# STB_MCU.net
KiCad netlist of a schematic drawn in Altium Designer
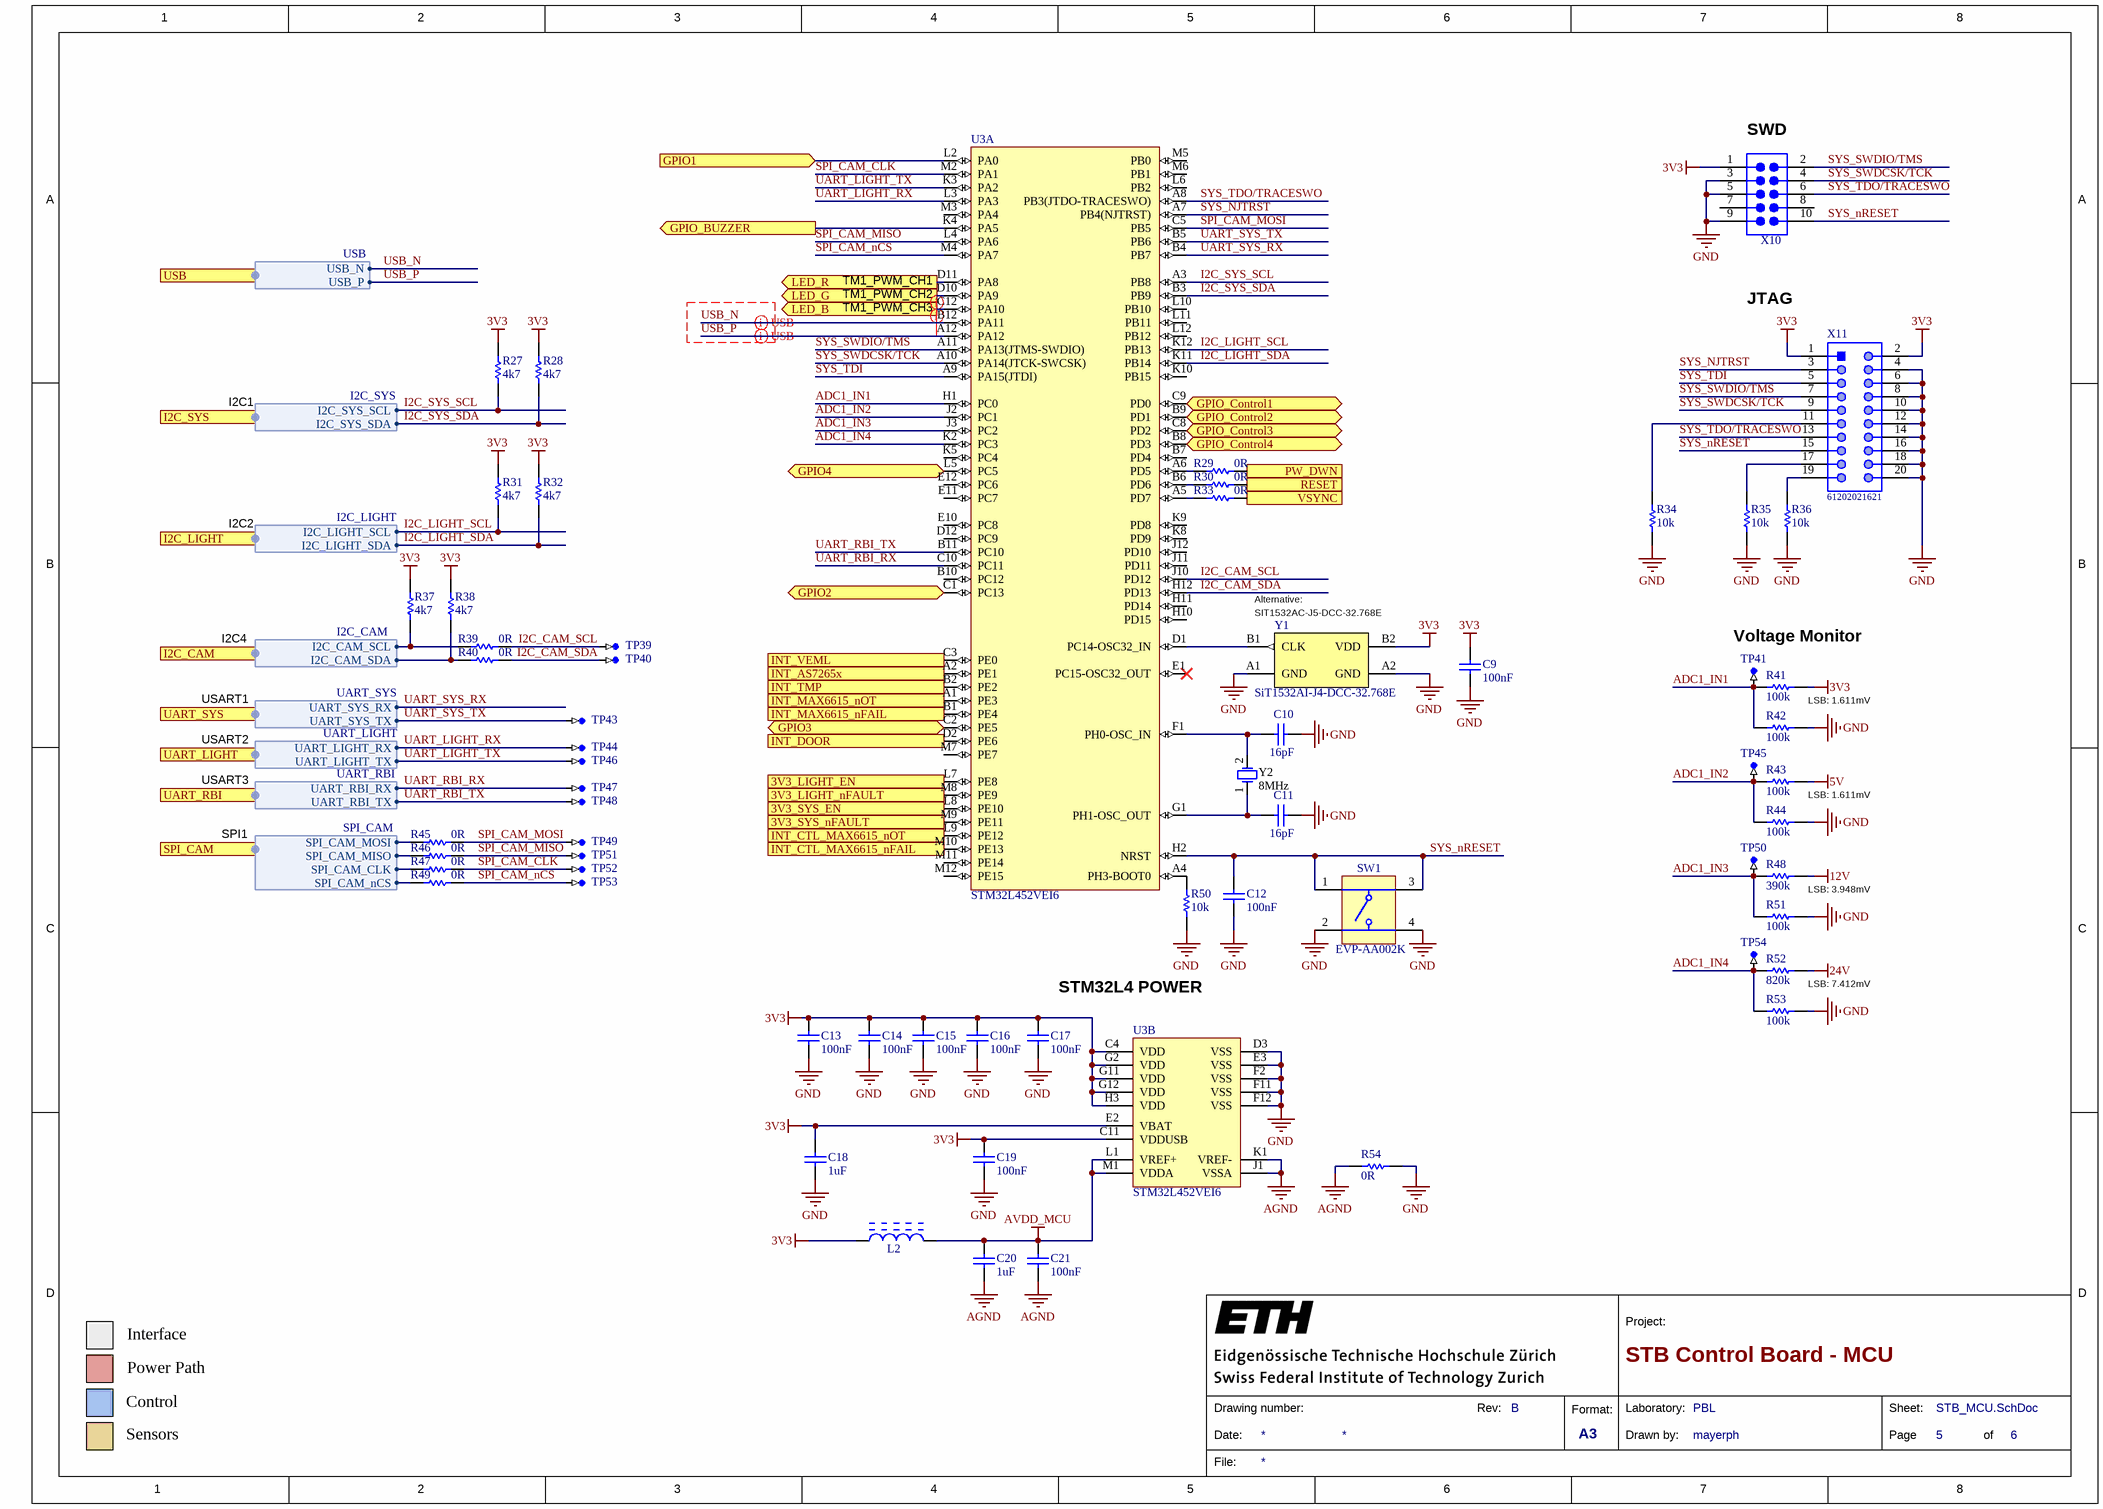
[diagram p0: STB_MCU.SchDoc]

(export (version "E")
  (design (tool "Eeschema 10.0.6"))
  (components
    (comp (ref "C9")
      (value "100nF")
      (footprint "CAPC1050X55X23LL05T13")
      (description "Chip Capacitor, 100 nF, +/- 10%, 16 V, -55 to 125 degC, 0402 (1005 Metric), RoHS, Tape and Reel")
      (fields
        (field (name "MANUFACTURER") "Samsung Electro-Mechanics")
        (field (name "MANUFACTURER PART NUMBER") "CL05B104KO5NNNC")
      )
      (libsource (lib "Altium Content Vault") (part "CAP-NP-2"))
    )
    (comp (ref "C10")
      (value "16pF")
      (footprint "CAPC1005X55X25LL05T10")
      (fields (field (name "MANUFACTURER") "Murata") (field (name "PART NUMBER") "GRM1555C1H160JA01D"))
      (libsource (lib "Altium Content Vault") (part "CAP"))
    )
    (comp (ref "C11")
      (value "16pF")
      (footprint "CAPC1005X55X25LL05T10")
      (fields (field (name "MANUFACTURER") "Murata") (field (name "PART NUMBER") "GRM1555C1H160JA01D"))
      (libsource (lib "Altium Content Vault") (part "CAP"))
    )
    (comp (ref "C12")
      (value "100nF")
      (footprint "CAPC1050X55X23LL05T13")
      (description "Chip Capacitor, 100 nF, +/- 10%, 16 V, -55 to 125 degC, 0402 (1005 Metric), RoHS, Tape and Reel")
      (fields
        (field (name "MANUFACTURER") "Samsung Electro-Mechanics")
        (field (name "MANUFACTURER PART NUMBER") "CL05B104KO5NNNC")
      )
      (libsource (lib "Altium Content Vault") (part "CAP-NP-2"))
    )
    (comp (ref "C13")
      (value "100nF")
      (footprint "CAPC1050X55X23LL05T13")
      (description "Chip Capacitor, 100 nF, +/- 10%, 16 V, -55 to 125 degC, 0402 (1005 Metric), RoHS, Tape and Reel")
      (fields
        (field (name "MANUFACTURER") "Samsung Electro-Mechanics")
        (field (name "MANUFACTURER PART NUMBER") "CL05B104KO5NNNC")
      )
      (libsource (lib "Altium Content Vault") (part "CAP-NP-2"))
    )
    (comp (ref "C14")
      (value "100nF")
      (footprint "CAPC1050X55X23LL05T13")
      (description "Chip Capacitor, 100 nF, +/- 10%, 16 V, -55 to 125 degC, 0402 (1005 Metric), RoHS, Tape and Reel")
      (fields
        (field (name "MANUFACTURER") "Samsung Electro-Mechanics")
        (field (name "MANUFACTURER PART NUMBER") "CL05B104KO5NNNC")
      )
      (libsource (lib "Altium Content Vault") (part "CAP-NP-2"))
    )
    (comp (ref "C15")
      (value "100nF")
      (footprint "CAPC1050X55X23LL05T13")
      (description "Chip Capacitor, 100 nF, +/- 10%, 16 V, -55 to 125 degC, 0402 (1005 Metric), RoHS, Tape and Reel")
      (fields
        (field (name "MANUFACTURER") "Samsung Electro-Mechanics")
        (field (name "MANUFACTURER PART NUMBER") "CL05B104KO5NNNC")
      )
      (libsource (lib "Altium Content Vault") (part "CAP-NP-2"))
    )
    (comp (ref "C16")
      (value "100nF")
      (footprint "CAPC1050X55X23LL05T13")
      (description "Chip Capacitor, 100 nF, +/- 10%, 16 V, -55 to 125 degC, 0402 (1005 Metric), RoHS, Tape and Reel")
      (fields
        (field (name "MANUFACTURER") "Samsung Electro-Mechanics")
        (field (name "MANUFACTURER PART NUMBER") "CL05B104KO5NNNC")
      )
      (libsource (lib "Altium Content Vault") (part "CAP-NP-2"))
    )
    (comp (ref "C17")
      (value "100nF")
      (footprint "CAPC1050X55X23LL05T13")
      (description "Chip Capacitor, 100 nF, +/- 10%, 16 V, -55 to 125 degC, 0402 (1005 Metric), RoHS, Tape and Reel")
      (fields
        (field (name "MANUFACTURER") "Samsung Electro-Mechanics")
        (field (name "MANUFACTURER PART NUMBER") "CL05B104KO5NNNC")
      )
      (libsource (lib "Altium Content Vault") (part "CAP-NP-2"))
    )
    (comp (ref "C18")
      (value "1uF")
      (footprint "CAPC1608X90X35LL15T15")
      (fields (field (name "MANUFACTURER") "Kemet") (field (name "PART NUMBER") "C0603C105K4RACTU"))
      (libsource (lib "Altium Content Vault") (part "CAP"))
    )
    (comp (ref "C19")
      (value "100nF")
      (footprint "CAPC1050X55X23LL05T13")
      (description "Chip Capacitor, 100 nF, +/- 10%, 16 V, -55 to 125 degC, 0402 (1005 Metric), RoHS, Tape and Reel")
      (fields
        (field (name "MANUFACTURER") "Samsung Electro-Mechanics")
        (field (name "MANUFACTURER PART NUMBER") "CL05B104KO5NNNC")
      )
      (libsource (lib "Altium Content Vault") (part "CAP-NP-2"))
    )
    (comp (ref "C20")
      (value "1uF")
      (footprint "CAPC1608X90X35LL15T15")
      (fields (field (name "MANUFACTURER") "Kemet") (field (name "PART NUMBER") "C0603C105K4RACTU"))
      (libsource (lib "Altium Content Vault") (part "CAP"))
    )
    (comp (ref "C21")
      (value "100nF")
      (footprint "CAPC1050X55X23LL05T13")
      (description "Chip Capacitor, 100 nF, +/- 10%, 16 V, -55 to 125 degC, 0402 (1005 Metric), RoHS, Tape and Reel")
      (fields
        (field (name "MANUFACTURER") "Samsung Electro-Mechanics")
        (field (name "MANUFACTURER PART NUMBER") "CL05B104KO5NNNC")
      )
      (libsource (lib "Altium Content Vault") (part "CAP-NP-2"))
    )
    (comp (ref "L2")
      (value "LI0402E300R-10")
      (footprint "INDC1005X07L")
      (description "30 Ohm 1 Power, Signal Line Ferrite Bead 0402 (1005 Metric) 500mA 300 mOhm Max DCR")
      (fields (field (name "MANUFACTURER") "Laird-Signal Integrity Products"))
      (libsource (lib "ETHZ Vault") (part "Ferrite Bead"))
    )
    (comp (ref "R27")
      (value "4k7")
      (footprint "RESC1005X40X25LL05T10")
      (fields
        (field (name "MANUFACTURER") "Yageo / Phycomp")
        (field (name "PART NUMBER") "RC0402FR-074K7L")
        (field (name "TOLERANCE") "1%")
      )
      (libsource (lib "Altium Content Vault") (part "RES"))
    )
    (comp (ref "R28")
      (value "4k7")
      (footprint "RESC1005X40X25LL05T10")
      (fields
        (field (name "MANUFACTURER") "Yageo / Phycomp")
        (field (name "PART NUMBER") "RC0402FR-074K7L")
        (field (name "TOLERANCE") "1%")
      )
      (libsource (lib "Altium Content Vault") (part "RES"))
    )
    (comp (ref "R29")
      (value "0R")
      (footprint "RESC1005X40X25LL05T10")
      (fields (field (name "MANUFACTURER") "Yageo / Phycomp") (field (name "PART NUMBER") "RC0402JR-070RL"))
      (libsource (lib "Altium Content Vault") (part "RES"))
    )
    (comp (ref "R30")
      (value "0R")
      (footprint "RESC1005X40X25LL05T10")
      (fields (field (name "MANUFACTURER") "Yageo / Phycomp") (field (name "PART NUMBER") "RC0402JR-070RL"))
      (libsource (lib "Altium Content Vault") (part "RES"))
    )
    (comp (ref "R31")
      (value "4k7")
      (footprint "RESC1005X40X25LL05T10")
      (fields
        (field (name "MANUFACTURER") "Yageo / Phycomp")
        (field (name "PART NUMBER") "RC0402FR-074K7L")
        (field (name "TOLERANCE") "1%")
      )
      (libsource (lib "Altium Content Vault") (part "RES"))
    )
    (comp (ref "R32")
      (value "4k7")
      (footprint "RESC1005X40X25LL05T10")
      (fields
        (field (name "MANUFACTURER") "Yageo / Phycomp")
        (field (name "PART NUMBER") "RC0402FR-074K7L")
        (field (name "TOLERANCE") "1%")
      )
      (libsource (lib "Altium Content Vault") (part "RES"))
    )
    (comp (ref "R33")
      (value "0R")
      (footprint "RESC1005X40X25LL05T10")
      (fields (field (name "MANUFACTURER") "Yageo / Phycomp") (field (name "PART NUMBER") "RC0402JR-070RL"))
      (libsource (lib "Altium Content Vault") (part "RES"))
    )
    (comp (ref "R34")
      (value "10k")
      (footprint "RESC1005X40X25LL05T05")
      (description "Chip Resistor, 10 KOhm, +/- 1%, 0.1 W, -55 to 155 degC, 0402 (1005 Metric), RoHS, Tape and Reel")
      (fields (field (name "TOLERANCE") "1%") (field (name "MANUFACTURER") "Panasonic"))
      (libsource (lib "Altium Content Vault") (part "RES-2"))
    )
    (comp (ref "R35")
      (value "10k")
      (footprint "RESC1005X40X25LL05T05")
      (description "Chip Resistor, 10 KOhm, +/- 1%, 0.1 W, -55 to 155 degC, 0402 (1005 Metric), RoHS, Tape and Reel")
      (fields (field (name "TOLERANCE") "1%") (field (name "MANUFACTURER") "Panasonic"))
      (libsource (lib "Altium Content Vault") (part "RES-2"))
    )
    (comp (ref "R36")
      (value "10k")
      (footprint "RESC1005X40X25LL05T05")
      (description "Chip Resistor, 10 KOhm, +/- 1%, 0.1 W, -55 to 155 degC, 0402 (1005 Metric), RoHS, Tape and Reel")
      (fields (field (name "TOLERANCE") "1%") (field (name "MANUFACTURER") "Panasonic"))
      (libsource (lib "Altium Content Vault") (part "RES-2"))
    )
    (comp (ref "R37")
      (value "4k7")
      (footprint "RESC1005X40X25LL05T10")
      (fields
        (field (name "MANUFACTURER") "Yageo / Phycomp")
        (field (name "PART NUMBER") "RC0402FR-074K7L")
        (field (name "TOLERANCE") "1%")
      )
      (libsource (lib "Altium Content Vault") (part "RES"))
    )
    (comp (ref "R38")
      (value "4k7")
      (footprint "RESC1005X40X25LL05T10")
      (fields
        (field (name "MANUFACTURER") "Yageo / Phycomp")
        (field (name "PART NUMBER") "RC0402FR-074K7L")
        (field (name "TOLERANCE") "1%")
      )
      (libsource (lib "Altium Content Vault") (part "RES"))
    )
    (comp (ref "R39")
      (value "0R")
      (footprint "RESC1005X40X25LL05T10")
      (fields (field (name "MANUFACTURER") "Yageo / Phycomp") (field (name "PART NUMBER") "RC0402JR-070RL"))
      (libsource (lib "Altium Content Vault") (part "RES"))
    )
    (comp (ref "R40")
      (value "0R")
      (footprint "RESC1005X40X25LL05T10")
      (fields (field (name "MANUFACTURER") "Yageo / Phycomp") (field (name "PART NUMBER") "RC0402JR-070RL"))
      (libsource (lib "Altium Content Vault") (part "RES"))
    )
    (comp (ref "R41")
      (value "100k")
      (footprint "RESC1005X40X25LL05T10")
      (fields
        (field (name "PART NUMBER") "RC0402FR-07100KL")
        (field (name "MANUFACTURER") "Yageo / Phycomp")
        (field (name "TOLERANCE") "1%")
      )
      (libsource (lib "Altium Content Vault") (part "RES"))
    )
    (comp (ref "R42")
      (value "100k")
      (footprint "RESC1005X40X25LL05T10")
      (fields
        (field (name "PART NUMBER") "RC0402FR-07100KL")
        (field (name "MANUFACTURER") "Yageo / Phycomp")
        (field (name "TOLERANCE") "1%")
      )
      (libsource (lib "Altium Content Vault") (part "RES"))
    )
    (comp (ref "R43")
      (value "100k")
      (footprint "RESC1005X40X25LL05T10")
      (fields
        (field (name "PART NUMBER") "RC0402FR-07100KL")
        (field (name "MANUFACTURER") "Yageo / Phycomp")
        (field (name "TOLERANCE") "1%")
      )
      (libsource (lib "Altium Content Vault") (part "RES"))
    )
    (comp (ref "R44")
      (value "100k")
      (footprint "RESC1005X40X25LL05T10")
      (fields
        (field (name "PART NUMBER") "RC0402FR-07100KL")
        (field (name "MANUFACTURER") "Yageo / Phycomp")
        (field (name "TOLERANCE") "1%")
      )
      (libsource (lib "Altium Content Vault") (part "RES"))
    )
    (comp (ref "R45")
      (value "0R")
      (footprint "RESC1005X40X25LL05T10")
      (fields (field (name "MANUFACTURER") "Yageo / Phycomp") (field (name "PART NUMBER") "RC0402JR-070RL"))
      (libsource (lib "Altium Content Vault") (part "RES"))
    )
    (comp (ref "R46")
      (value "0R")
      (footprint "RESC1005X40X25LL05T10")
      (fields (field (name "MANUFACTURER") "Yageo / Phycomp") (field (name "PART NUMBER") "RC0402JR-070RL"))
      (libsource (lib "Altium Content Vault") (part "RES"))
    )
    (comp (ref "R47")
      (value "0R")
      (footprint "RESC1005X40X25LL05T10")
      (fields (field (name "MANUFACTURER") "Yageo / Phycomp") (field (name "PART NUMBER") "RC0402JR-070RL"))
      (libsource (lib "Altium Content Vault") (part "RES"))
    )
    (comp (ref "R48")
      (value "390k")
      (footprint "RESC1005X40X25LL05T05")
      (fields
        (field (name "PART NUMBER") "ERJ2RKF3903X")
        (field (name "MANUFACTURER") "Panasonic")
        (field (name "MANUFACTURER PART NUMBER") "ERJ-2RKF3903X")
      )
      (libsource (lib "Altium Content Vault") (part "RES"))
    )
    (comp (ref "R49")
      (value "0R")
      (footprint "RESC1005X40X25LL05T10")
      (fields (field (name "MANUFACTURER") "Yageo / Phycomp") (field (name "PART NUMBER") "RC0402JR-070RL"))
      (libsource (lib "Altium Content Vault") (part "RES"))
    )
    (comp (ref "R50")
      (value "10k")
      (footprint "RESC1005X40X25LL05T05")
      (description "Chip Resistor, 10 KOhm, +/- 1%, 0.1 W, -55 to 155 degC, 0402 (1005 Metric), RoHS, Tape and Reel")
      (fields (field (name "TOLERANCE") "1%") (field (name "MANUFACTURER") "Panasonic"))
      (libsource (lib "Altium Content Vault") (part "RES-2"))
    )
    (comp (ref "R51")
      (value "100k")
      (footprint "RESC1005X40X25LL05T10")
      (fields
        (field (name "PART NUMBER") "RC0402FR-07100KL")
        (field (name "MANUFACTURER") "Yageo / Phycomp")
        (field (name "TOLERANCE") "1%")
      )
      (libsource (lib "Altium Content Vault") (part "RES"))
    )
    (comp (ref "R52")
      (value "820k")
      (footprint "RESC1005X40X25LL05T05")
      (fields
        (field (name "PART NUMBER") "CRCW0402820KFKED")
        (field (name "MANUFACTURER") "Vishay Dale")
        (field (name "TOLERANCE") "1%")
      )
      (libsource (lib "Altium Content Vault") (part "RES"))
    )
    (comp (ref "R53")
      (value "100k")
      (footprint "RESC1005X40X25LL05T10")
      (fields
        (field (name "PART NUMBER") "RC0402FR-07100KL")
        (field (name "MANUFACTURER") "Yageo / Phycomp")
        (field (name "TOLERANCE") "1%")
      )
      (libsource (lib "Altium Content Vault") (part "RES"))
    )
    (comp (ref "R54")
      (value "0R")
      (footprint "RESC1005X40X25LL05T10")
      (fields (field (name "MANUFACTURER") "Yageo / Phycomp") (field (name "PART NUMBER") "RC0402JR-070RL"))
      (libsource (lib "Altium Content Vault") (part "RES"))
    )
    (comp (ref "SW1")
      (value "EVP-AA002K")
      (footprint "PNSC-EVPAA_V")
      (description "Light Touch Switch, 100 mOhm, -40 to 85 degC, 4-Pin SMD, RoHS, Tape and Reel")
      (fields (field (name "MANUFACTURER") "Panasonic"))
      (libsource (lib "Altium Content Vault") (part "SW-SPST-4"))
    )
    (comp (ref "TP39")
      (value "TP_1mm")
      (footprint "TP-SM-C-100")
      (description "testPoint 1mm")
      (libsource (lib "STB_Schlib") (part "testPoint_1mm"))
    )
    (comp (ref "TP40")
      (value "TP_1mm")
      (footprint "TP-SM-C-100")
      (description "testPoint 1mm")
      (libsource (lib "STB_Schlib") (part "testPoint_1mm"))
    )
    (comp (ref "TP41")
      (value "TP_1mm")
      (footprint "TP-SM-C-100")
      (description "testPoint 1mm")
      (libsource (lib "STB_Schlib") (part "testPoint_1mm"))
    )
    (comp (ref "TP43")
      (value "TP_1mm")
      (footprint "TP-SM-C-100")
      (description "testPoint 1mm")
      (libsource (lib "STB_Schlib") (part "testPoint_1mm"))
    )
    (comp (ref "TP44")
      (value "TP_1mm")
      (footprint "TP-SM-C-100")
      (description "testPoint 1mm")
      (libsource (lib "STB_Schlib") (part "testPoint_1mm"))
    )
    (comp (ref "TP45")
      (value "TP_1mm")
      (footprint "TP-SM-C-100")
      (description "testPoint 1mm")
      (libsource (lib "STB_Schlib") (part "testPoint_1mm"))
    )
    (comp (ref "TP46")
      (value "TP_1mm")
      (footprint "TP-SM-C-100")
      (description "testPoint 1mm")
      (libsource (lib "STB_Schlib") (part "testPoint_1mm"))
    )
    (comp (ref "TP47")
      (value "TP_1mm")
      (footprint "TP-SM-C-100")
      (description "testPoint 1mm")
      (libsource (lib "STB_Schlib") (part "testPoint_1mm"))
    )
    (comp (ref "TP48")
      (value "TP_1mm")
      (footprint "TP-SM-C-100")
      (description "testPoint 1mm")
      (libsource (lib "STB_Schlib") (part "testPoint_1mm"))
    )
    (comp (ref "TP49")
      (value "TP_1mm")
      (footprint "TP-SM-C-100")
      (description "testPoint 1mm")
      (libsource (lib "STB_Schlib") (part "testPoint_1mm"))
    )
    (comp (ref "TP50")
      (value "TP_1mm")
      (footprint "TP-SM-C-100")
      (description "testPoint 1mm")
      (libsource (lib "STB_Schlib") (part "testPoint_1mm"))
    )
    (comp (ref "TP51")
      (value "TP_1mm")
      (footprint "TP-SM-C-100")
      (description "testPoint 1mm")
      (libsource (lib "STB_Schlib") (part "testPoint_1mm"))
    )
    (comp (ref "TP52")
      (value "TP_1mm")
      (footprint "TP-SM-C-100")
      (description "testPoint 1mm")
      (libsource (lib "STB_Schlib") (part "testPoint_1mm"))
    )
    (comp (ref "TP53")
      (value "TP_1mm")
      (footprint "TP-SM-C-100")
      (description "testPoint 1mm")
      (libsource (lib "STB_Schlib") (part "testPoint_1mm"))
    )
    (comp (ref "TP54")
      (value "TP_1mm")
      (footprint "TP-SM-C-100")
      (description "testPoint 1mm")
      (libsource (lib "STB_Schlib") (part "testPoint_1mm"))
    )
    (comp (ref "U3")
      (value "STM32L452VEI6")
      (footprint "UFBGA100")
      (description "IC MCU 32BIT 512KB FLASH 100UFBGA")
      (fields (field (name "MANUFACTURER") "STMicroelectronics"))
      (libsource (lib "") (part "STM32L452-UFBGA-100_1"))
    )
    (comp (ref "X10")
      (value "3220-10-0100-00")
      (footprint "3220-10-0100-00")
      (description "BOX HEADER, 0.050 5x2 POS")
      (fields (field (name "MANUFACTURER") "CNC Tech"))
      (libsource (lib "ETHZ Vault") (part "CON-5x2-Male"))
    )
    (comp (ref "X11")
      (value "61202021621")
      (footprint "61202021621")
      (description "Male Box Header WR-BHD, THT, Vertical, pitch 2.54 mm, 20 pins")
      (fields (field (name "MANUFACTURER") "Wurth Elektronik") (field (name "PUBLISHER") "WurthElektronik"))
      (libsource (lib "Altium Content Vault") (part "WE-CN-2P-M-R20"))
    )
    (comp (ref "Y1")
      (value "SiT1532AI-J4-DCC-32.768E")
      (footprint "4-UFBGA")
      (fields (field (name "MANUFACTURER") "SiTime"))
      (libsource (lib "ETHZ Vault") (part "SiT1552"))
    )
    (comp (ref "Y2")
      (value "8MHz")
      (footprint "NDK-NX3225GD-8MHZ-STD-CRA-3_V")
      (description "Crystal Unit, 8 MHz, 8 pF, -40 to 150 degC, 2-Pin SMD, RoHS, Tape and Reel")
      (fields
        (field (name "MANUFACTURER") "NDK")
        (field (name "MANUFACTURER PART NUMBER") "NX3225GD-8MHZ-STD-CRA-3")
      )
      (libsource (lib "Altium Content Vault") (part "XTAL-1-2-2"))
    )
  )
  (nets
    (net (code "9") (name "/3V3_LIGHT_EN") (class "Default")
      (node (ref "U3") (pin "L7") (pinfunction "PE8_L7") (pintype "bidirectional"))
    )
    (net (code "10") (name "/3V3_LIGHT_nFAULT") (class "Default")
      (node (ref "U3") (pin "M8") (pinfunction "PE9_M8") (pintype "bidirectional"))
    )
    (net (code "11") (name "/3V3_SYS_EN") (class "Default")
      (node (ref "U3") (pin "L8") (pinfunction "PE10_L8") (pintype "bidirectional"))
    )
    (net (code "12") (name "/3V3_SYS_nFAULT") (class "Default")
      (node (ref "U3") (pin "M9") (pinfunction "PE11_M9") (pintype "bidirectional"))
    )
    (net (code "13") (name "/ADC1_IN1") (class "Default")
      (node (ref "R41") (pin "2") (pinfunction "2_2") (pintype "passive"))
      (node (ref "R42") (pin "2") (pinfunction "2_2") (pintype "passive"))
      (node (ref "TP41") (pin "TP") (pinfunction "TP_TP") (pintype "input"))
      (node (ref "U3") (pin "H1") (pinfunction "PC0_H1") (pintype "bidirectional"))
    )
    (net (code "14") (name "/ADC1_IN2") (class "Default")
      (node (ref "R43") (pin "2") (pinfunction "2_2") (pintype "passive"))
      (node (ref "R44") (pin "2") (pinfunction "2_2") (pintype "passive"))
      (node (ref "TP45") (pin "TP") (pinfunction "TP_TP") (pintype "input"))
      (node (ref "U3") (pin "J2") (pinfunction "PC1_J2") (pintype "bidirectional"))
    )
    (net (code "15") (name "/ADC1_IN3") (class "Default")
      (node (ref "R48") (pin "1") (pinfunction "1_1") (pintype "passive"))
      (node (ref "R51") (pin "2") (pinfunction "2_2") (pintype "passive"))
      (node (ref "TP50") (pin "TP") (pinfunction "TP_TP") (pintype "input"))
      (node (ref "U3") (pin "J3") (pinfunction "PC2_J3") (pintype "bidirectional"))
    )
    (net (code "16") (name "/ADC1_IN4") (class "Default")
      (node (ref "R52") (pin "1") (pinfunction "1_1") (pintype "passive"))
      (node (ref "R53") (pin "2") (pinfunction "2_2") (pintype "passive"))
      (node (ref "TP54") (pin "TP") (pinfunction "TP_TP") (pintype "input"))
      (node (ref "U3") (pin "K2") (pinfunction "PC3_K2") (pintype "bidirectional"))
    )
    (net (code "17") (name "/GPIO1") (class "Default")
      (node (ref "U3") (pin "L2") (pinfunction "PA0_L2") (pintype "bidirectional"))
    )
    (net (code "18") (name "/GPIO2") (class "Default")
      (node (ref "U3") (pin "C1") (pinfunction "PC13_C1") (pintype "bidirectional"))
    )
    (net (code "19") (name "/GPIO3") (class "Default")
      (node (ref "U3") (pin "C2") (pinfunction "PE5_C2") (pintype "bidirectional"))
    )
    (net (code "20") (name "/GPIO4") (class "Default")
      (node (ref "U3") (pin "L5") (pinfunction "PC5_L5") (pintype "bidirectional"))
    )
    (net (code "21") (name "/GPIO_BUZZER") (class "Default")
      (node (ref "U3") (pin "K4") (pinfunction "PA5_K4") (pintype "bidirectional"))
    )
    (net (code "22") (name "/GPIO_Control1") (class "Default")
      (node (ref "U3") (pin "C9") (pinfunction "PD0_C9") (pintype "bidirectional"))
    )
    (net (code "23") (name "/GPIO_Control2") (class "Default")
      (node (ref "U3") (pin "B9") (pinfunction "PD1_B9") (pintype "bidirectional"))
    )
    (net (code "24") (name "/GPIO_Control3") (class "Default")
      (node (ref "U3") (pin "C8") (pinfunction "PD2_C8") (pintype "bidirectional"))
    )
    (net (code "25") (name "/GPIO_Control4") (class "Default")
      (node (ref "U3") (pin "B8") (pinfunction "PD3_B8") (pintype "bidirectional"))
    )
    (net (code "26") (name "/I2C_CAM_SCL") (class "Default")
      (node (ref "R39") (pin "2") (pinfunction "2_2") (pintype "passive"))
      (node (ref "TP39") (pin "TP") (pinfunction "TP_TP") (pintype "input"))
      (node (ref "U3") (pin "J10") (pinfunction "PD12_J10") (pintype "bidirectional"))
    )
    (net (code "27") (name "/I2C_CAM_SDA") (class "Default")
      (node (ref "R40") (pin "2") (pinfunction "2_2") (pintype "passive"))
      (node (ref "TP40") (pin "TP") (pinfunction "TP_TP") (pintype "input"))
      (node (ref "U3") (pin "H12") (pinfunction "PD13_H12") (pintype "bidirectional"))
    )
    (net (code "28") (name "/I2C_LIGHT_SCL") (class "Default")
      (node (ref "R31") (pin "1") (pinfunction "1_1") (pintype "passive"))
      (node (ref "U3") (pin "K12") (pinfunction "PB13_K12") (pintype "bidirectional"))
    )
    (net (code "29") (name "/I2C_LIGHT_SDA") (class "Default")
      (node (ref "R32") (pin "1") (pinfunction "1_1") (pintype "passive"))
      (node (ref "U3") (pin "K11") (pinfunction "PB14_K11") (pintype "bidirectional"))
    )
    (net (code "30") (name "/I2C_SYS_SCL") (class "Default")
      (node (ref "R27") (pin "1") (pinfunction "1_1") (pintype "passive"))
      (node (ref "U3") (pin "A3") (pinfunction "PB8_A3") (pintype "bidirectional"))
    )
    (net (code "31") (name "/I2C_SYS_SDA") (class "Default")
      (node (ref "R28") (pin "1") (pinfunction "1_1") (pintype "passive"))
      (node (ref "U3") (pin "B3") (pinfunction "PB9_B3") (pintype "bidirectional"))
    )
    (net (code "32") (name "/INT_AS7265x") (class "Default")
      (node (ref "U3") (pin "A2") (pinfunction "PE1_A2") (pintype "bidirectional"))
    )
    (net (code "33") (name "/INT_CTL_MAX6615_nFAIL") (class "Default")
      (node (ref "U3") (pin "M10") (pinfunction "PE13_M10") (pintype "bidirectional"))
    )
    (net (code "34") (name "/INT_CTL_MAX6615_nOT") (class "Default")
      (node (ref "U3") (pin "L9") (pinfunction "PE12_L9") (pintype "bidirectional"))
    )
    (net (code "35") (name "/INT_DOOR") (class "Default")
      (node (ref "U3") (pin "D2") (pinfunction "PE6_D2") (pintype "bidirectional"))
    )
    (net (code "36") (name "/INT_MAX6615_nFAIL") (class "Default")
      (node (ref "U3") (pin "B1") (pinfunction "PE4_B1") (pintype "bidirectional"))
    )
    (net (code "37") (name "/INT_MAX6615_nOT") (class "Default")
      (node (ref "U3") (pin "A1") (pinfunction "PE3_A1") (pintype "bidirectional"))
    )
    (net (code "38") (name "/INT_TMP") (class "Default")
      (node (ref "U3") (pin "B2") (pinfunction "PE2_B2") (pintype "bidirectional"))
    )
    (net (code "39") (name "/INT_VEML") (class "Default")
      (node (ref "U3") (pin "C3") (pinfunction "PE0_C3") (pintype "bidirectional"))
    )
    (net (code "40") (name "/LED_B") (class "Default")
      (node (ref "U3") (pin "C12") (pinfunction "PA10_C12") (pintype "bidirectional"))
    )
    (net (code "41") (name "/LED_G") (class "Default")
      (node (ref "U3") (pin "D10") (pinfunction "PA9_D10") (pintype "bidirectional"))
    )
    (net (code "42") (name "/LED_R") (class "Default")
      (node (ref "U3") (pin "D11") (pinfunction "PA8_D11") (pintype "bidirectional"))
    )
    (net (code "43") (name "/PW_DWN") (class "Default")
      (node (ref "R29") (pin "2") (pinfunction "2_2") (pintype "passive"))
    )
    (net (code "44") (name "/RESET") (class "Default")
      (node (ref "R30") (pin "2") (pinfunction "2_2") (pintype "passive"))
    )
    (net (code "45") (name "/SPI_CAM_CLK") (class "Default")
      (node (ref "R47") (pin "2") (pinfunction "2_2") (pintype "passive"))
      (node (ref "TP52") (pin "TP") (pinfunction "TP_TP") (pintype "input"))
      (node (ref "U3") (pin "M2") (pinfunction "PA1_M2") (pintype "bidirectional"))
    )
    (net (code "46") (name "/SPI_CAM_MISO") (class "Default")
      (node (ref "R46") (pin "2") (pinfunction "2_2") (pintype "passive"))
      (node (ref "TP51") (pin "TP") (pinfunction "TP_TP") (pintype "input"))
      (node (ref "U3") (pin "L4") (pinfunction "PA6_L4") (pintype "bidirectional"))
    )
    (net (code "47") (name "/SPI_CAM_MOSI") (class "Default")
      (node (ref "R45") (pin "2") (pinfunction "2_2") (pintype "passive"))
      (node (ref "TP49") (pin "TP") (pinfunction "TP_TP") (pintype "input"))
      (node (ref "U3") (pin "C5") (pinfunction "PB5_C5") (pintype "bidirectional"))
    )
    (net (code "48") (name "/SPI_CAM_nCS") (class "Default")
      (node (ref "R49") (pin "2") (pinfunction "2_2") (pintype "passive"))
      (node (ref "TP53") (pin "TP") (pinfunction "TP_TP") (pintype "input"))
      (node (ref "U3") (pin "M4") (pinfunction "PA7_M4") (pintype "bidirectional"))
    )
    (net (code "49") (name "/SYS_NJTRST") (class "Default")
      (node (ref "U3") (pin "A7") (pinfunction "PB4(NJTRST)_A7") (pintype "bidirectional"))
      (node (ref "X11") (pin "3") (pinfunction "3_3") (pintype "passive"))
    )
    (net (code "50") (name "/SYS_SWDCSK{slash}TCK") (class "Default")
      (node (ref "U3") (pin "A10") (pinfunction "PA14(JTCK-SWCSK)_A10") (pintype "bidirectional"))
      (node (ref "X10") (pin "4") (pinfunction "4_4") (pintype "passive"))
      (node (ref "X11") (pin "9") (pinfunction "9_9") (pintype "passive"))
    )
    (net (code "51") (name "/SYS_SWDIO{slash}TMS") (class "Default")
      (node (ref "U3") (pin "A11") (pinfunction "PA13(JTMS-SWDIO)_A11") (pintype "bidirectional"))
      (node (ref "X10") (pin "2") (pinfunction "2_2") (pintype "passive"))
      (node (ref "X11") (pin "7") (pinfunction "7_7") (pintype "passive"))
    )
    (net (code "52") (name "/SYS_TDI") (class "Default")
      (node (ref "U3") (pin "A9") (pinfunction "PA15(JTDI)_A9") (pintype "bidirectional"))
      (node (ref "X11") (pin "5") (pinfunction "5_5") (pintype "passive"))
    )
    (net (code "53") (name "/SYS_TDO{slash}TRACESWO") (class "Default")
      (node (ref "U3") (pin "A8") (pinfunction "PB3(JTDO-TRACESWO)_A8") (pintype "bidirectional"))
      (node (ref "X10") (pin "6") (pinfunction "6_6") (pintype "passive"))
      (node (ref "X11") (pin "13") (pinfunction "13_13") (pintype "passive"))
    )
    (net (code "54") (name "/SYS_nRESET") (class "Default")
      (node (ref "C12") (pin "2") (pinfunction "2_2") (pintype "passive"))
      (node (ref "SW1") (pin "1") (pinfunction "A_1") (pintype "passive"))
      (node (ref "SW1") (pin "3") (pinfunction "A'_3") (pintype "passive"))
      (node (ref "U3") (pin "H2") (pinfunction "NRST_H2") (pintype "bidirectional"))
      (node (ref "X10") (pin "10") (pinfunction "10_10") (pintype "passive"))
      (node (ref "X11") (pin "15") (pinfunction "15_15") (pintype "passive"))
    )
    (net (code "55") (name "/UART_LIGHT_RX") (class "Default")
      (node (ref "TP44") (pin "TP") (pinfunction "TP_TP") (pintype "input"))
      (node (ref "U3") (pin "L3") (pinfunction "PA3_L3") (pintype "bidirectional"))
    )
    (net (code "56") (name "/UART_LIGHT_TX") (class "Default")
      (node (ref "TP46") (pin "TP") (pinfunction "TP_TP") (pintype "input"))
      (node (ref "U3") (pin "K3") (pinfunction "PA2_K3") (pintype "bidirectional"))
    )
    (net (code "57") (name "/UART_RBI_RX") (class "Default")
      (node (ref "TP47") (pin "TP") (pinfunction "TP_TP") (pintype "input"))
      (node (ref "U3") (pin "C10") (pinfunction "PC11_C10") (pintype "bidirectional"))
    )
    (net (code "58") (name "/UART_RBI_TX") (class "Default")
      (node (ref "TP48") (pin "TP") (pinfunction "TP_TP") (pintype "input"))
      (node (ref "U3") (pin "B11") (pinfunction "PC10_B11") (pintype "bidirectional"))
    )
    (net (code "59") (name "/UART_SYS_RX") (class "Default")
      (node (ref "U3") (pin "B4") (pinfunction "PB7_B4") (pintype "bidirectional"))
    )
    (net (code "60") (name "/UART_SYS_TX") (class "Default")
      (node (ref "TP43") (pin "TP") (pinfunction "TP_TP") (pintype "input"))
      (node (ref "U3") (pin "B5") (pinfunction "PB6_B5") (pintype "bidirectional"))
    )
    (net (code "61") (name "/USB_N") (class "Default")
      (node (ref "U3") (pin "B12") (pinfunction "PA11_B12") (pintype "bidirectional"))
    )
    (net (code "62") (name "/USB_P") (class "Default")
      (node (ref "U3") (pin "A12") (pinfunction "PA12_A12") (pintype "bidirectional"))
    )
    (net (code "63") (name "/VSYNC") (class "Default")
      (node (ref "R33") (pin "2") (pinfunction "2_2") (pintype "passive"))
    )
    (net (code "72") (name "3V3") (class "Default")
      (node (ref "C13") (pin "2") (pinfunction "2_2") (pintype "passive"))
      (node (ref "C14") (pin "2") (pinfunction "2_2") (pintype "passive"))
      (node (ref "C15") (pin "2") (pinfunction "2_2") (pintype "passive"))
      (node (ref "C16") (pin "2") (pinfunction "2_2") (pintype "passive"))
      (node (ref "C17") (pin "2") (pinfunction "2_2") (pintype "passive"))
      (node (ref "C18") (pin "2") (pinfunction "2_2") (pintype "passive"))
      (node (ref "C19") (pin "2") (pinfunction "2_2") (pintype "passive"))
      (node (ref "C9") (pin "2") (pinfunction "2_2") (pintype "passive"))
      (node (ref "L2") (pin "1") (pinfunction "1_1") (pintype "passive"))
      (node (ref "R27") (pin "2") (pinfunction "2_2") (pintype "passive"))
      (node (ref "R28") (pin "2") (pinfunction "2_2") (pintype "passive"))
      (node (ref "R31") (pin "2") (pinfunction "2_2") (pintype "passive"))
      (node (ref "R32") (pin "2") (pinfunction "2_2") (pintype "passive"))
      (node (ref "R37") (pin "2") (pinfunction "2_2") (pintype "passive"))
      (node (ref "R38") (pin "2") (pinfunction "2_2") (pintype "passive"))
      (node (ref "R41") (pin "1") (pinfunction "1_1") (pintype "passive"))
      (node (ref "U3") (pin "C11") (pinfunction "VDDUSB_C11") (pintype "power_in"))
      (node (ref "U3") (pin "C4") (pinfunction "VDD_C4") (pintype "power_in"))
      (node (ref "U3") (pin "E2") (pinfunction "VBAT_E2") (pintype "power_in"))
      (node (ref "U3") (pin "G11") (pinfunction "VDD_G11") (pintype "power_in"))
      (node (ref "U3") (pin "G12") (pinfunction "VDD_G12") (pintype "power_in"))
      (node (ref "U3") (pin "G2") (pinfunction "VDD_G2") (pintype "power_in"))
      (node (ref "U3") (pin "H3") (pinfunction "VDD_H3") (pintype "power_in"))
      (node (ref "X10") (pin "1") (pinfunction "1_1") (pintype "passive"))
      (node (ref "X11") (pin "1") (pinfunction "1_1") (pintype "passive"))
      (node (ref "X11") (pin "2") (pinfunction "2_2") (pintype "passive"))
      (node (ref "Y1") (pin "B2") (pinfunction "VDD_B2") (pintype "power_in"))
    )
    (net (code "73") (name "5V") (class "Default")
      (node (ref "R43") (pin "1") (pinfunction "1_1") (pintype "passive"))
    )
    (net (code "74") (name "12V") (class "Default")
      (node (ref "R48") (pin "2") (pinfunction "2_2") (pintype "passive"))
    )
    (net (code "75") (name "24V") (class "Default")
      (node (ref "R52") (pin "2") (pinfunction "2_2") (pintype "passive"))
    )
    (net (code "76") (name "AGND") (class "Default")
      (node (ref "C20") (pin "1") (pinfunction "1_1") (pintype "passive"))
      (node (ref "C21") (pin "1") (pinfunction "1_1") (pintype "passive"))
      (node (ref "R54") (pin "1") (pinfunction "1_1") (pintype "passive"))
      (node (ref "U3") (pin "J1") (pinfunction "VSSA_J1") (pintype "power_in"))
      (node (ref "U3") (pin "K1") (pinfunction "VREF-_K1") (pintype "power_in"))
    )
    (net (code "77") (name "AVDD_MCU") (class "Default")
      (node (ref "C20") (pin "2") (pinfunction "2_2") (pintype "passive"))
      (node (ref "C21") (pin "2") (pinfunction "2_2") (pintype "passive"))
      (node (ref "L2") (pin "2") (pinfunction "2_2") (pintype "passive"))
      (node (ref "U3") (pin "L1") (pinfunction "VREF+_L1") (pintype "power_in"))
      (node (ref "U3") (pin "M1") (pinfunction "VDDA_M1") (pintype "power_in"))
    )
    (net (code "78") (name "GND") (class "Default")
      (node (ref "C10") (pin "2") (pinfunction "2_2") (pintype "passive"))
      (node (ref "C11") (pin "2") (pinfunction "2_2") (pintype "passive"))
      (node (ref "C12") (pin "1") (pinfunction "1_1") (pintype "passive"))
      (node (ref "C13") (pin "1") (pinfunction "1_1") (pintype "passive"))
      (node (ref "C14") (pin "1") (pinfunction "1_1") (pintype "passive"))
      (node (ref "C15") (pin "1") (pinfunction "1_1") (pintype "passive"))
      (node (ref "C16") (pin "1") (pinfunction "1_1") (pintype "passive"))
      (node (ref "C17") (pin "1") (pinfunction "1_1") (pintype "passive"))
      (node (ref "C18") (pin "1") (pinfunction "1_1") (pintype "passive"))
      (node (ref "C19") (pin "1") (pinfunction "1_1") (pintype "passive"))
      (node (ref "C9") (pin "1") (pinfunction "1_1") (pintype "passive"))
      (node (ref "R34") (pin "1") (pinfunction "1_1") (pintype "passive"))
      (node (ref "R35") (pin "1") (pinfunction "1_1") (pintype "passive"))
      (node (ref "R36") (pin "1") (pinfunction "1_1") (pintype "passive"))
      (node (ref "R42") (pin "1") (pinfunction "1_1") (pintype "passive"))
      (node (ref "R44") (pin "1") (pinfunction "1_1") (pintype "passive"))
      (node (ref "R50") (pin "1") (pinfunction "1_1") (pintype "passive"))
      (node (ref "R51") (pin "1") (pinfunction "1_1") (pintype "passive"))
      (node (ref "R53") (pin "1") (pinfunction "1_1") (pintype "passive"))
      (node (ref "R54") (pin "2") (pinfunction "2_2") (pintype "passive"))
      (node (ref "SW1") (pin "2") (pinfunction "B_2") (pintype "passive"))
      (node (ref "SW1") (pin "4") (pinfunction "B'_4") (pintype "passive"))
      (node (ref "U3") (pin "D3") (pinfunction "VSS_D3") (pintype "power_in"))
      (node (ref "U3") (pin "E3") (pinfunction "VSS_E3") (pintype "power_in"))
      (node (ref "U3") (pin "F11") (pinfunction "VSS_F11") (pintype "power_in"))
      (node (ref "U3") (pin "F12") (pinfunction "VSS_F12") (pintype "power_in"))
      (node (ref "U3") (pin "F2") (pinfunction "VSS_F2") (pintype "power_in"))
      (node (ref "X10") (pin "3") (pinfunction "3_3") (pintype "passive"))
      (node (ref "X10") (pin "5") (pinfunction "5_5") (pintype "passive"))
      (node (ref "X10") (pin "9") (pinfunction "9_9") (pintype "passive"))
      (node (ref "X11") (pin "10") (pinfunction "10_10") (pintype "passive"))
      (node (ref "X11") (pin "12") (pinfunction "12_12") (pintype "passive"))
      (node (ref "X11") (pin "14") (pinfunction "14_14") (pintype "passive"))
      (node (ref "X11") (pin "16") (pinfunction "16_16") (pintype "passive"))
      (node (ref "X11") (pin "18") (pinfunction "18_18") (pintype "passive"))
      (node (ref "X11") (pin "20") (pinfunction "20_20") (pintype "passive"))
      (node (ref "X11") (pin "4") (pinfunction "4_4") (pintype "passive"))
      (node (ref "X11") (pin "6") (pinfunction "6_6") (pintype "passive"))
      (node (ref "X11") (pin "8") (pinfunction "8_8") (pintype "passive"))
      (node (ref "Y1") (pin "A1") (pinfunction "GND_A1") (pintype "power_in"))
      (node (ref "Y1") (pin "A2") (pinfunction "GND_A2") (pintype "power_in"))
    )
    (net (code "79") (name "Net-(R34-Pad2)") (class "Default")
      (node (ref "R34") (pin "2") (pinfunction "2_2") (pintype "passive"))
      (node (ref "X11") (pin "11") (pinfunction "11_11") (pintype "passive"))
    )
    (net (code "80") (name "Net-(R35-Pad2)") (class "Default")
      (node (ref "R35") (pin "2") (pinfunction "2_2") (pintype "passive"))
      (node (ref "X11") (pin "17") (pinfunction "17_17") (pintype "passive"))
    )
    (net (code "81") (name "Net-(R36-Pad2)") (class "Default")
      (node (ref "R36") (pin "2") (pinfunction "2_2") (pintype "passive"))
      (node (ref "X11") (pin "19") (pinfunction "19_19") (pintype "passive"))
    )
    (net (code "82") (name "Net-(R37-Pad1)") (class "Default")
      (node (ref "R37") (pin "1") (pinfunction "1_1") (pintype "passive"))
      (node (ref "R39") (pin "1") (pinfunction "1_1") (pintype "passive"))
    )
    (net (code "83") (name "Net-(R38-Pad1)") (class "Default")
      (node (ref "R38") (pin "1") (pinfunction "1_1") (pintype "passive"))
      (node (ref "R40") (pin "1") (pinfunction "1_1") (pintype "passive"))
    )
    (net (code "84") (name "Net-(U3A-PC14-OSC32_IN)") (class "Default")
      (node (ref "U3") (pin "D1") (pinfunction "PC14-OSC32_IN_D1") (pintype "bidirectional"))
      (node (ref "Y1") (pin "B1") (pinfunction "CLK_B1") (pintype "output"))
    )
    (net (code "85") (name "Net-(U3A-PD5)") (class "Default")
      (node (ref "R29") (pin "1") (pinfunction "1_1") (pintype "passive"))
      (node (ref "U3") (pin "A6") (pinfunction "PD5_A6") (pintype "bidirectional"))
    )
    (net (code "86") (name "Net-(U3A-PD6)") (class "Default")
      (node (ref "R30") (pin "1") (pinfunction "1_1") (pintype "passive"))
      (node (ref "U3") (pin "B6") (pinfunction "PD6_B6") (pintype "bidirectional"))
    )
    (net (code "87") (name "Net-(U3A-PD7)") (class "Default")
      (node (ref "R33") (pin "1") (pinfunction "1_1") (pintype "passive"))
      (node (ref "U3") (pin "A5") (pinfunction "PD7_A5") (pintype "bidirectional"))
    )
    (net (code "88") (name "Net-(U3A-PH0-OSC_IN)") (class "Default")
      (node (ref "C10") (pin "1") (pinfunction "1_1") (pintype "passive"))
      (node (ref "U3") (pin "F1") (pinfunction "PH0-OSC_IN_F1") (pintype "bidirectional"))
      (node (ref "Y2") (pin "2") (pinfunction "2_2") (pintype "passive"))
    )
    (net (code "89") (name "Net-(U3A-PH1-OSC_OUT)") (class "Default")
      (node (ref "C11") (pin "1") (pinfunction "1_1") (pintype "passive"))
      (node (ref "U3") (pin "G1") (pinfunction "PH1-OSC_OUT_G1") (pintype "bidirectional"))
      (node (ref "Y2") (pin "1") (pinfunction "1_1") (pintype "passive"))
    )
    (net (code "90") (name "Net-(U3A-PH3-BOOT0)") (class "Default")
      (node (ref "R50") (pin "2") (pinfunction "2_2") (pintype "passive"))
      (node (ref "U3") (pin "A4") (pinfunction "PH3-BOOT0_A4") (pintype "bidirectional"))
    )
    (net (code "91") (name "unconnected-(R45-Pad1)") (class "Default")
      (node (ref "R45") (pin "1") (pinfunction "1_1") (pintype "passive"))
    )
    (net (code "92") (name "unconnected-(R46-Pad1)") (class "Default")
      (node (ref "R46") (pin "1") (pinfunction "1_1") (pintype "passive"))
    )
    (net (code "93") (name "unconnected-(R47-Pad1)") (class "Default")
      (node (ref "R47") (pin "1") (pinfunction "1_1") (pintype "passive"))
    )
    (net (code "94") (name "unconnected-(R49-Pad1)") (class "Default")
      (node (ref "R49") (pin "1") (pinfunction "1_1") (pintype "passive"))
    )
    (net (code "95") (name "unconnected-(U3A-PA4-PadM3)") (class "Default")
      (node (ref "U3") (pin "M3") (pinfunction "PA4_M3") (pintype "bidirectional"))
    )
    (net (code "96") (name "unconnected-(U3A-PB0-PadM5)") (class "Default")
      (node (ref "U3") (pin "M5") (pinfunction "PB0_M5") (pintype "bidirectional"))
    )
    (net (code "97") (name "unconnected-(U3A-PB1-PadM6)") (class "Default")
      (node (ref "U3") (pin "M6") (pinfunction "PB1_M6") (pintype "bidirectional"))
    )
    (net (code "98") (name "unconnected-(U3A-PB2-PadL6)") (class "Default")
      (node (ref "U3") (pin "L6") (pinfunction "PB2_L6") (pintype "bidirectional"))
    )
    (net (code "99") (name "unconnected-(U3A-PB10-PadL10)") (class "Default")
      (node (ref "U3") (pin "L10") (pinfunction "PB10_L10") (pintype "bidirectional"))
    )
    (net (code "100") (name "unconnected-(U3A-PB11-PadL11)") (class "Default")
      (node (ref "U3") (pin "L11") (pinfunction "PB11_L11") (pintype "bidirectional"))
    )
    (net (code "101") (name "unconnected-(U3A-PB12-PadL12)") (class "Default")
      (node (ref "U3") (pin "L12") (pinfunction "PB12_L12") (pintype "bidirectional"))
    )
    (net (code "102") (name "unconnected-(U3A-PB15-PadK10)") (class "Default")
      (node (ref "U3") (pin "K10") (pinfunction "PB15_K10") (pintype "bidirectional"))
    )
    (net (code "103") (name "unconnected-(U3A-PC4-PadK5)") (class "Default")
      (node (ref "U3") (pin "K5") (pinfunction "PC4_K5") (pintype "bidirectional"))
    )
    (net (code "104") (name "unconnected-(U3A-PC6-PadE12)") (class "Default")
      (node (ref "U3") (pin "E12") (pinfunction "PC6_E12") (pintype "bidirectional"))
    )
    (net (code "105") (name "unconnected-(U3A-PC7-PadE11)") (class "Default")
      (node (ref "U3") (pin "E11") (pinfunction "PC7_E11") (pintype "bidirectional"))
    )
    (net (code "106") (name "unconnected-(U3A-PC8-PadE10)") (class "Default")
      (node (ref "U3") (pin "E10") (pinfunction "PC8_E10") (pintype "bidirectional"))
    )
    (net (code "107") (name "unconnected-(U3A-PC9-PadD12)") (class "Default")
      (node (ref "U3") (pin "D12") (pinfunction "PC9_D12") (pintype "bidirectional"))
    )
    (net (code "108") (name "unconnected-(U3A-PC12-PadB10)") (class "Default")
      (node (ref "U3") (pin "B10") (pinfunction "PC12_B10") (pintype "bidirectional"))
    )
    (net (code "109") (name "unconnected-(U3A-PC15-OSC32_OUT-PadE1)") (class "Default")
      (node (ref "U3") (pin "E1") (pinfunction "PC15-OSC32_OUT_E1") (pintype "bidirectional+no_connect"))
    )
    (net (code "110") (name "unconnected-(U3A-PD4-PadB7)") (class "Default")
      (node (ref "U3") (pin "B7") (pinfunction "PD4_B7") (pintype "bidirectional"))
    )
    (net (code "111") (name "unconnected-(U3A-PD8-PadK9)") (class "Default")
      (node (ref "U3") (pin "K9") (pinfunction "PD8_K9") (pintype "bidirectional"))
    )
    (net (code "112") (name "unconnected-(U3A-PD9-PadK8)") (class "Default")
      (node (ref "U3") (pin "K8") (pinfunction "PD9_K8") (pintype "bidirectional"))
    )
    (net (code "113") (name "unconnected-(U3A-PD10-PadJ12)") (class "Default")
      (node (ref "U3") (pin "J12") (pinfunction "PD10_J12") (pintype "bidirectional"))
    )
    (net (code "114") (name "unconnected-(U3A-PD11-PadJ11)") (class "Default")
      (node (ref "U3") (pin "J11") (pinfunction "PD11_J11") (pintype "bidirectional"))
    )
    (net (code "115") (name "unconnected-(U3A-PD14-PadH11)") (class "Default")
      (node (ref "U3") (pin "H11") (pinfunction "PD14_H11") (pintype "bidirectional"))
    )
    (net (code "116") (name "unconnected-(U3A-PD15-PadH10)") (class "Default")
      (node (ref "U3") (pin "H10") (pinfunction "PD15_H10") (pintype "bidirectional"))
    )
    (net (code "117") (name "unconnected-(U3A-PE7-PadM7)") (class "Default")
      (node (ref "U3") (pin "M7") (pinfunction "PE7_M7") (pintype "bidirectional"))
    )
    (net (code "118") (name "unconnected-(U3A-PE14-PadM11)") (class "Default")
      (node (ref "U3") (pin "M11") (pinfunction "PE14_M11") (pintype "bidirectional"))
    )
    (net (code "119") (name "unconnected-(U3A-PE15-PadM12)") (class "Default")
      (node (ref "U3") (pin "M12") (pinfunction "PE15_M12") (pintype "bidirectional"))
    )
    (net (code "120") (name "unconnected-(X10-Pad7)") (class "Default")
      (node (ref "X10") (pin "7") (pinfunction "7_7") (pintype "passive"))
    )
    (net (code "121") (name "unconnected-(X10-Pad8)") (class "Default")
      (node (ref "X10") (pin "8") (pinfunction "8_8") (pintype "passive"))
    )
  )
)
